# pulse_generator_pen.net
KiCad netlist of a schematic drawn in Altium Designer
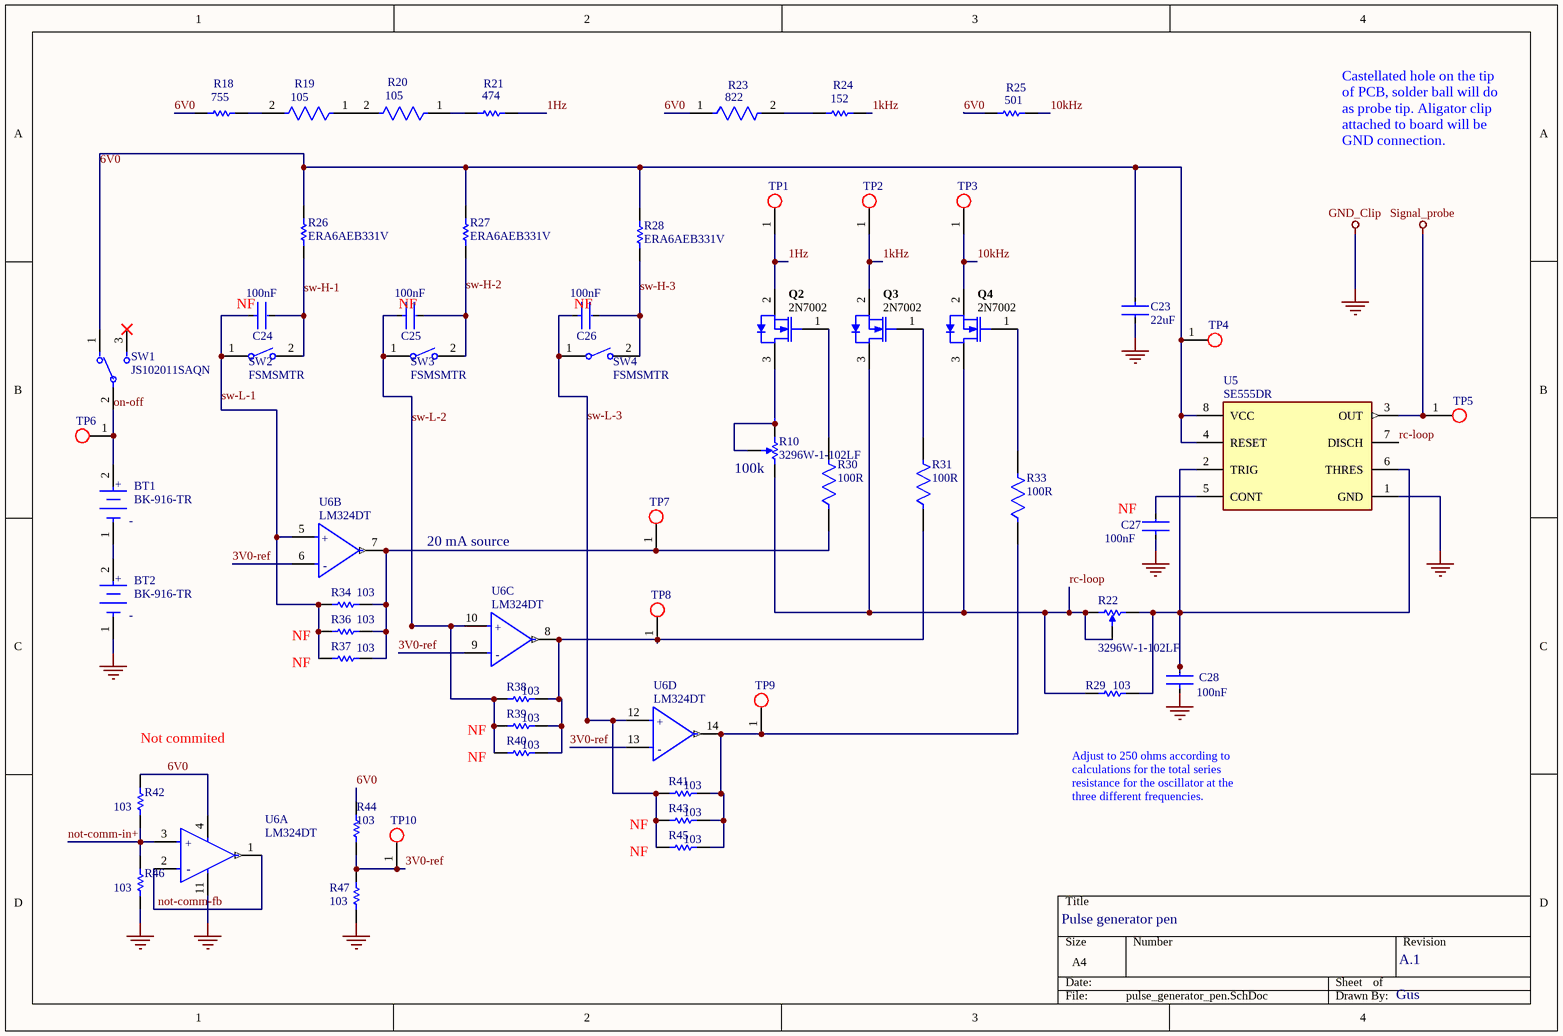
[diagram p0: pulse_generator_pen.SchDoc]

(export (version "E")
  (design (tool "Eeschema 10.0.6"))
  (components
    (comp (ref "BT1")
      (value "BK-916-TR")
      (footprint "FP-BK-916-TR-MFG")
      (description "BATTERY RETAINER COIN 12MM SMD")
      (libsource (lib "Altium Content Vault") (part "a5284bd3cf3b31494a5f032c79b9da8"))
    )
    (comp (ref "BT2")
      (value "BK-916-TR")
      (footprint "FP-BK-916-TR-MFG")
      (description "BATTERY RETAINER COIN 12MM SMD")
      (libsource (lib "Altium Content Vault") (part "a5284bd3cf3b31494a5f032c79b9da8"))
    )
    (comp (ref "C23")
      (value "C2012X5R1V226M125AC")
      (footprint "FP-C2012-125-0_2-IPC_A")
      (description "Multilayer Ceramic Capacitors 22μF ±20% 35V X5R SMD 0805")
      (fields (field (name "TOLERANCE") "20%") (field (name "CAPACITANCE") "22uF"))
      (libsource (lib "Altium Content Vault") (part "b4654b650e69147ec39a6b967a45e02"))
    )
    (comp (ref "C24")
      (value "CL21B104KBCNNNC")
      (footprint "FP-CL21-IPC_A")
      (description "CL21 Series 0805 100nF 50V ±10% Tolerance X7R Multilayer Ceramic Chip Capacitor")
      (fields
        (field (name "TOLERANCE") "10%")
        (field (name "CAPACITANCE") "100nF")
        (field (name "VOLTAGE") "50V")
      )
      (libsource (lib "Altium Content Vault") (part "b4654b650e69147ec39a6b967a45e02"))
    )
    (comp (ref "C25")
      (value "CL21B104KBCNNNC")
      (footprint "FP-CL21-IPC_A")
      (description "CL21 Series 0805 100nF 50V ±10% Tolerance X7R Multilayer Ceramic Chip Capacitor")
      (fields
        (field (name "TOLERANCE") "10%")
        (field (name "CAPACITANCE") "100nF")
        (field (name "VOLTAGE") "50V")
      )
      (libsource (lib "Altium Content Vault") (part "b4654b650e69147ec39a6b967a45e02"))
    )
    (comp (ref "C26")
      (value "CL21B104KBCNNNC")
      (footprint "FP-CL21-IPC_A")
      (description "CL21 Series 0805 100nF 50V ±10% Tolerance X7R Multilayer Ceramic Chip Capacitor")
      (fields
        (field (name "TOLERANCE") "10%")
        (field (name "CAPACITANCE") "100nF")
        (field (name "VOLTAGE") "50V")
      )
      (libsource (lib "Altium Content Vault") (part "b4654b650e69147ec39a6b967a45e02"))
    )
    (comp (ref "C27")
      (value "CL21B104KBCNNNC")
      (footprint "FP-CL21-IPC_A")
      (description "CL21 Series 0805 100nF 50V ±10% Tolerance X7R Multilayer Ceramic Chip Capacitor")
      (fields
        (field (name "TOLERANCE") "10%")
        (field (name "CAPACITANCE") "100nF")
        (field (name "VOLTAGE") "50V")
      )
      (libsource (lib "Altium Content Vault") (part "b4654b650e69147ec39a6b967a45e02"))
    )
    (comp (ref "C28")
      (value "CL21B104KBCNNNC")
      (footprint "FP-CL21-IPC_A")
      (description "CL21 Series 0805 100nF 50V ±10% Tolerance X7R Multilayer Ceramic Chip Capacitor")
      (fields
        (field (name "TOLERANCE") "10%")
        (field (name "CAPACITANCE") "100nF")
        (field (name "VOLTAGE") "50V")
      )
      (libsource (lib "Altium Content Vault") (part "b4654b650e69147ec39a6b967a45e02"))
    )
    (comp (ref "Q2")
      (value "2N7002")
      (footprint "INF-PG-SOT23_M")
      (fields (field (name "MANUFACTURER") "Infineon"))
      (libsource (lib "Altium Content Vault") (part "INF-NDMOS-GSD-3"))
    )
    (comp (ref "Q3")
      (value "2N7002")
      (footprint "INF-PG-SOT23_M")
      (fields (field (name "MANUFACTURER") "Infineon"))
      (libsource (lib "Altium Content Vault") (part "INF-NDMOS-GSD-3"))
    )
    (comp (ref "Q4")
      (value "2N7002")
      (footprint "INF-PG-SOT23_M")
      (fields (field (name "MANUFACTURER") "Infineon"))
      (libsource (lib "Altium Content Vault") (part "INF-NDMOS-GSD-3"))
    )
    (comp (ref "R10")
      (value "3296W-1-102LF")
      (footprint "BOUR-3296W-1-3")
      (description "Square Trimpot(R) Trimming Potentiometer, 1000 Ohm, -55 to 125 degC, 3-Pin THD, RoHS, Tube")
      (fields (field (name "TOLERANCE") "1%"))
      (libsource (lib "Altium Content Vault") (part "RES-ADJ-3"))
    )
    (comp (ref "R18")
      (value "CRCW08057M50JNEA")
      (footprint "RESC2013X50X30LL20T20")
      (fields (field (name "MANUFACTURER") "Vishay Dale") (field (name "RESISTANCE") "755"))
      (libsource (lib "Altium Content Vault") (part "RES"))
    )
    (comp (ref "R19")
      (value "ERJ-6ENF1004V")
      (footprint "FP-ERJ6EN-IPC_A")
      (description "RES SMD 1M OHM 1% 1/8W 0805")
      (fields (field (name "RESISTANCE") "105") (field (name "TOLERANCE") "1%"))
      (libsource (lib "Altium Content Vault") (part "1029c3af85768c4190bb7ad29bc67b5"))
    )
    (comp (ref "R20")
      (value "ERJ-6ENF1004V")
      (footprint "FP-ERJ6EN-IPC_A")
      (description "RES SMD 1M OHM 1% 1/8W 0805")
      (fields (field (name "RESISTANCE") "105") (field (name "TOLERANCE") "1%"))
      (libsource (lib "Altium Content Vault") (part "1029c3af85768c4190bb7ad29bc67b5"))
    )
    (comp (ref "R21")
      (value "ERJ6ENF4703V")
      (footprint "RESC2013X70X40ML20T20")
      (fields (field (name "MANUFACTURER") "Panasonic") (field (name "RESISTANCE") "474"))
      (libsource (lib "Altium Content Vault") (part "RES"))
    )
    (comp (ref "R22")
      (value "3296W-1-102LF")
      (footprint "BOUR-3296W-1-3")
      (description "Square Trimpot(R) Trimming Potentiometer, 1000 Ohm, -55 to 125 degC, 3-Pin THD, RoHS, Tube")
      (fields (field (name "TOLERANCE") "1%"))
      (libsource (lib "Altium Content Vault") (part "RES-ADJ-3"))
    )
    (comp (ref "R23")
      (value "RC2012J822CS")
      (footprint "FP-RC2012-IPC_A")
      (description "Res Thick Film 0805 8.2kΩ 5% 0.125W ±100ppm/°C Molded SMD T/R")
      (fields (field (name "RESISTANCE") "822") (field (name "TOLERANCE") "5%"))
      (libsource (lib "Altium Content Vault") (part "1029c3af85768c4190bb7ad29bc67b5"))
    )
    (comp (ref "R24")
      (value "RC0805FR-071K5L")
      (footprint "RESC2013X60X35LL10T20")
      (description "RES 1.50K OHM 1/8W 1% 0805 SMD")
      (fields (field (name "MANUFACTURER") "Yageo") (field (name "RESISTANCE") "152"))
      (libsource (lib "") (part "RES-2_1"))
    )
    (comp (ref "R25")
      (value "WSLP0805R0500FEA")
      (footprint "RESC2013X58X38LL25T25")
      (fields (field (name "MANUFACTURER") "Vishay Dale") (field (name "RESISTANCE") "501"))
      (libsource (lib "Altium Content Vault") (part "RES"))
    )
    (comp (ref "R26")
      (value "ERA6AEB331V")
      (footprint "RESC2013X60X40LL20T25")
      (fields (field (name "MANUFACTURER") "Panasonic"))
      (libsource (lib "Altium Content Vault") (part "RES"))
    )
    (comp (ref "R27")
      (value "ERA6AEB331V")
      (footprint "RESC2013X60X40LL20T25")
      (fields (field (name "MANUFACTURER") "Panasonic"))
      (libsource (lib "Altium Content Vault") (part "RES"))
    )
    (comp (ref "R28")
      (value "ERA6AEB331V")
      (footprint "RESC2013X60X40LL20T25")
      (fields (field (name "MANUFACTURER") "Panasonic"))
      (libsource (lib "Altium Content Vault") (part "RES"))
    )
    (comp (ref "R29")
      (value "RC0805FR-0710KL")
      (footprint "RESC2013X60X35NL10T20")
      (description "Chip Resistor, 10 KOhm, +/- 1%, 0.125 W, -55 to 155 degC, 0805 (2012 Metric), RoHS, Tape and Reel")
      (fields (field (name "MANUFACTURER") "Yageo") (field (name "RESISTANCE") "103"))
      (libsource (lib "Altium Content Vault") (part "RES-2"))
    )
    (comp (ref "R30")
      (value "CRCW0805100RFKEAHP")
      (footprint "FP-CRCW0805-HPe3-IPC_A")
      (description "RES Thick Film, 100Ω, 1%, 0.5W, 100ppm/°C, 0805")
      (fields (field (name "TOLERANCE") "1%") (field (name "RESISTANCE") "100R"))
      (libsource (lib "") (part "1029c3af85768c4190bb7ad29bc67b5_1"))
    )
    (comp (ref "R31")
      (value "CRCW0805100RFKEAHP")
      (footprint "FP-CRCW0805-HPe3-IPC_A")
      (description "RES Thick Film, 100Ω, 1%, 0.5W, 100ppm/°C, 0805")
      (fields (field (name "TOLERANCE") "1%") (field (name "RESISTANCE") "100R"))
      (libsource (lib "") (part "1029c3af85768c4190bb7ad29bc67b5_1"))
    )
    (comp (ref "R33")
      (value "CRCW0805100RFKEAHP")
      (footprint "FP-CRCW0805-HPe3-IPC_A")
      (description "RES Thick Film, 100Ω, 1%, 0.5W, 100ppm/°C, 0805")
      (fields (field (name "TOLERANCE") "1%") (field (name "RESISTANCE") "100R"))
      (libsource (lib "") (part "1029c3af85768c4190bb7ad29bc67b5_1"))
    )
    (comp (ref "R34")
      (value "RC0805FR-0710KL")
      (footprint "RESC2013X60X35NL10T20")
      (description "Chip Resistor, 10 KOhm, +/- 1%, 0.125 W, -55 to 155 degC, 0805 (2012 Metric), RoHS, Tape and Reel")
      (fields (field (name "MANUFACTURER") "Yageo") (field (name "RESISTANCE") "103"))
      (libsource (lib "Altium Content Vault") (part "RES-2"))
    )
    (comp (ref "R36")
      (value "RC0805FR-0710KL")
      (footprint "RESC2013X60X35NL10T20")
      (description "Chip Resistor, 10 KOhm, +/- 1%, 0.125 W, -55 to 155 degC, 0805 (2012 Metric), RoHS, Tape and Reel")
      (fields (field (name "MANUFACTURER") "Yageo") (field (name "RESISTANCE") "103"))
      (libsource (lib "Altium Content Vault") (part "RES-2"))
    )
    (comp (ref "R37")
      (value "RC0805FR-0710KL")
      (footprint "RESC2013X60X35NL10T20")
      (description "Chip Resistor, 10 KOhm, +/- 1%, 0.125 W, -55 to 155 degC, 0805 (2012 Metric), RoHS, Tape and Reel")
      (fields (field (name "MANUFACTURER") "Yageo") (field (name "RESISTANCE") "103"))
      (libsource (lib "Altium Content Vault") (part "RES-2"))
    )
    (comp (ref "R38")
      (value "RC0805FR-0710KL")
      (footprint "RESC2013X60X35NL10T20")
      (description "Chip Resistor, 10 KOhm, +/- 1%, 0.125 W, -55 to 155 degC, 0805 (2012 Metric), RoHS, Tape and Reel")
      (fields (field (name "MANUFACTURER") "Yageo") (field (name "RESISTANCE") "103"))
      (libsource (lib "Altium Content Vault") (part "RES-2"))
    )
    (comp (ref "R39")
      (value "RC0805FR-0710KL")
      (footprint "RESC2013X60X35NL10T20")
      (description "Chip Resistor, 10 KOhm, +/- 1%, 0.125 W, -55 to 155 degC, 0805 (2012 Metric), RoHS, Tape and Reel")
      (fields (field (name "MANUFACTURER") "Yageo") (field (name "RESISTANCE") "103"))
      (libsource (lib "Altium Content Vault") (part "RES-2"))
    )
    (comp (ref "R40")
      (value "RC0805FR-0710KL")
      (footprint "RESC2013X60X35NL10T20")
      (description "Chip Resistor, 10 KOhm, +/- 1%, 0.125 W, -55 to 155 degC, 0805 (2012 Metric), RoHS, Tape and Reel")
      (fields (field (name "MANUFACTURER") "Yageo") (field (name "RESISTANCE") "103"))
      (libsource (lib "Altium Content Vault") (part "RES-2"))
    )
    (comp (ref "R41")
      (value "RC0805FR-0710KL")
      (footprint "RESC2013X60X35NL10T20")
      (description "Chip Resistor, 10 KOhm, +/- 1%, 0.125 W, -55 to 155 degC, 0805 (2012 Metric), RoHS, Tape and Reel")
      (fields (field (name "MANUFACTURER") "Yageo") (field (name "RESISTANCE") "103"))
      (libsource (lib "Altium Content Vault") (part "RES-2"))
    )
    (comp (ref "R42")
      (value "RC0805FR-0710KL")
      (footprint "RESC2013X60X35NL10T20")
      (description "Chip Resistor, 10 KOhm, +/- 1%, 0.125 W, -55 to 155 degC, 0805 (2012 Metric), RoHS, Tape and Reel")
      (fields (field (name "MANUFACTURER") "Yageo") (field (name "RESISTANCE") "103"))
      (libsource (lib "Altium Content Vault") (part "RES-2"))
    )
    (comp (ref "R43")
      (value "RC0805FR-0710KL")
      (footprint "RESC2013X60X35NL10T20")
      (description "Chip Resistor, 10 KOhm, +/- 1%, 0.125 W, -55 to 155 degC, 0805 (2012 Metric), RoHS, Tape and Reel")
      (fields (field (name "MANUFACTURER") "Yageo") (field (name "RESISTANCE") "103"))
      (libsource (lib "Altium Content Vault") (part "RES-2"))
    )
    (comp (ref "R44")
      (value "RC0805FR-0710KL")
      (footprint "RESC2013X60X35NL10T20")
      (description "Chip Resistor, 10 KOhm, +/- 1%, 0.125 W, -55 to 155 degC, 0805 (2012 Metric), RoHS, Tape and Reel")
      (fields (field (name "MANUFACTURER") "Yageo") (field (name "RESISTANCE") "103"))
      (libsource (lib "Altium Content Vault") (part "RES-2"))
    )
    (comp (ref "R45")
      (value "RC0805FR-0710KL")
      (footprint "RESC2013X60X35NL10T20")
      (description "Chip Resistor, 10 KOhm, +/- 1%, 0.125 W, -55 to 155 degC, 0805 (2012 Metric), RoHS, Tape and Reel")
      (fields (field (name "MANUFACTURER") "Yageo") (field (name "RESISTANCE") "103"))
      (libsource (lib "Altium Content Vault") (part "RES-2"))
    )
    (comp (ref "R46")
      (value "RC0805FR-0710KL")
      (footprint "RESC2013X60X35NL10T20")
      (description "Chip Resistor, 10 KOhm, +/- 1%, 0.125 W, -55 to 155 degC, 0805 (2012 Metric), RoHS, Tape and Reel")
      (fields (field (name "MANUFACTURER") "Yageo") (field (name "RESISTANCE") "103"))
      (libsource (lib "Altium Content Vault") (part "RES-2"))
    )
    (comp (ref "R47")
      (value "RC0805FR-0710KL")
      (footprint "RESC2013X60X35NL10T20")
      (description "Chip Resistor, 10 KOhm, +/- 1%, 0.125 W, -55 to 155 degC, 0805 (2012 Metric), RoHS, Tape and Reel")
      (fields (field (name "MANUFACTURER") "Yageo") (field (name "RESISTANCE") "103"))
      (libsource (lib "Altium Content Vault") (part "RES-2"))
    )
    (comp (ref "SW1")
      (value "JS102011SAQN")
      (footprint "FP-JS102011SAQN-MFG")
      (description "SWITCH SLIDE SPDT 300MA 6V")
      (libsource (lib "Altium Content Vault") (part "39e195cbbadc85d1df0d7eb6847d379"))
    )
    (comp (ref "SW2")
      (value "FSMSMTR")
      (footprint "TECO-FSMSMTR_V")
      (description "FSMSM Push Button Switch, 50 mA, -35 to 85 degC, 2-Pin SMD, RoHS, Tape and Reel")
      (fields (field (name "MANUFACTURER") "TE Connectivity"))
      (libsource (lib "Altium Content Vault") (part "SW-SPST-2_C"))
    )
    (comp (ref "SW3")
      (value "FSMSMTR")
      (footprint "TECO-FSMSMTR_V")
      (description "FSMSM Push Button Switch, 50 mA, -35 to 85 degC, 2-Pin SMD, RoHS, Tape and Reel")
      (fields (field (name "MANUFACTURER") "TE Connectivity"))
      (libsource (lib "Altium Content Vault") (part "SW-SPST-2_C"))
    )
    (comp (ref "SW4")
      (value "FSMSMTR")
      (footprint "TECO-FSMSMTR_V")
      (description "FSMSM Push Button Switch, 50 mA, -35 to 85 degC, 2-Pin SMD, RoHS, Tape and Reel")
      (fields (field (name "MANUFACTURER") "TE Connectivity"))
      (libsource (lib "Altium Content Vault") (part "SW-SPST-2_C"))
    )
    (comp (ref "TP1")
      (value "TP_opening")
      (footprint "New footprint 1")
      (description "Soldermask opening or top layer pad for testing purposes")
      (libsource (lib "Cetys University") (part "TP1"))
    )
    (comp (ref "TP2")
      (value "TP_opening")
      (footprint "New footprint 1")
      (description "Soldermask opening or top layer pad for testing purposes")
      (libsource (lib "Cetys University") (part "TP1"))
    )
    (comp (ref "TP3")
      (value "TP_opening")
      (footprint "New footprint 1")
      (description "Soldermask opening or top layer pad for testing purposes")
      (libsource (lib "Cetys University") (part "TP1"))
    )
    (comp (ref "TP4")
      (value "TP_opening")
      (footprint "New footprint 1")
      (description "Soldermask opening or top layer pad for testing purposes")
      (libsource (lib "Cetys University") (part "TP1"))
    )
    (comp (ref "TP5")
      (value "TP_opening")
      (footprint "New footprint 1")
      (description "Soldermask opening or top layer pad for testing purposes")
      (libsource (lib "Cetys University") (part "TP1"))
    )
    (comp (ref "TP6")
      (value "TP_opening")
      (footprint "New footprint 1")
      (description "Soldermask opening or top layer pad for testing purposes")
      (libsource (lib "Cetys University") (part "TP1"))
    )
    (comp (ref "TP7")
      (value "TP_opening")
      (footprint "New footprint 1")
      (description "Soldermask opening or top layer pad for testing purposes")
      (libsource (lib "Cetys University") (part "TP1"))
    )
    (comp (ref "TP8")
      (value "TP_opening")
      (footprint "New footprint 1")
      (description "Soldermask opening or top layer pad for testing purposes")
      (libsource (lib "Cetys University") (part "TP1"))
    )
    (comp (ref "TP9")
      (value "TP_opening")
      (footprint "New footprint 1")
      (description "Soldermask opening or top layer pad for testing purposes")
      (libsource (lib "Cetys University") (part "TP1"))
    )
    (comp (ref "TP10")
      (value "TP_opening")
      (footprint "New footprint 1")
      (description "Soldermask opening or top layer pad for testing purposes")
      (libsource (lib "Cetys University") (part "TP1"))
    )
    (comp (ref "U5")
      (value "SE555DR")
      (footprint "FP-D0008A-MFG")
      (description "IC OSC SGL TIMER 100KHZ 8-SOIC")
      (libsource (lib "Altium Content Vault") (part "dd5b8434f2346953fd8290325fbf3de"))
    )
    (comp (ref "U6")
      (value "LM324DT")
      (footprint "FP-SO-14-MFG")
      (description "IC OPAMP GP 4 CIRCUIT 14SO")
      (fields
        (field (name "OCTOPART") "https://octopart.com/lm324dt-stmicroelectronics-39579146")
        (field (name "MANUFACTURER") "STMicroelectronics")
      )
      (libsource (lib "Altium Content Vault") (part "a065ef67e5aa9ef3942d43d6008d043"))
    )
  )
  (nets
    (net (code "1") (name "/1Hz") (class "Default")
      (node (ref "Q2") (pin "2") (pinfunction "SOURCE_2") (pintype "passive"))
      (node (ref "R21") (pin "2") (pinfunction "2_2") (pintype "passive"))
      (node (ref "TP1") (pin "1") (pinfunction "1_1") (pintype "passive"))
    )
    (net (code "2") (name "/1kHz") (class "Default")
      (node (ref "Q3") (pin "2") (pinfunction "SOURCE_2") (pintype "passive"))
      (node (ref "R24") (pin "2") (pinfunction "2_2") (pintype "passive"))
      (node (ref "TP2") (pin "1") (pinfunction "1_1") (pintype "passive"))
    )
    (net (code "3") (name "/3V0-ref") (class "Default")
      (node (ref "R44") (pin "1") (pinfunction "1_1") (pintype "passive"))
      (node (ref "R47") (pin "2") (pinfunction "2_2") (pintype "passive"))
      (node (ref "TP10") (pin "1") (pinfunction "1_1") (pintype "passive"))
      (node (ref "U6") (pin "13") (pinfunction "Inverting_Input_4_13") (pintype "tri_state"))
      (node (ref "U6") (pin "6") (pinfunction "Inverting_Input_2_6") (pintype "tri_state"))
      (node (ref "U6") (pin "9") (pinfunction "Inverting_Input_3_9") (pintype "tri_state"))
    )
    (net (code "4") (name "/6V0") (class "Default")
      (node (ref "C23") (pin "1") (pinfunction "1_1") (pintype "passive"))
      (node (ref "R18") (pin "2") (pinfunction "2_2") (pintype "passive"))
      (node (ref "R23") (pin "1") (pinfunction "1_1") (pintype "passive"))
      (node (ref "R25") (pin "1") (pinfunction "1_1") (pintype "passive"))
      (node (ref "R26") (pin "1") (pinfunction "1_1") (pintype "passive"))
      (node (ref "R27") (pin "1") (pinfunction "1_1") (pintype "passive"))
      (node (ref "R28") (pin "1") (pinfunction "1_1") (pintype "passive"))
      (node (ref "R42") (pin "2") (pinfunction "2_2") (pintype "passive"))
      (node (ref "R44") (pin "2") (pinfunction "2_2") (pintype "passive"))
      (node (ref "SW1") (pin "1") (pinfunction "1_1") (pintype "passive"))
      (node (ref "TP4") (pin "1") (pinfunction "1_1") (pintype "passive"))
      (node (ref "U5") (pin "4") (pinfunction "RESET_4") (pintype "passive"))
      (node (ref "U5") (pin "8") (pinfunction "VCC_8") (pintype "power_in"))
      (node (ref "U6") (pin "4") (pinfunction "VCC+_4") (pintype "power_in"))
    )
    (net (code "5") (name "/10kHz") (class "Default")
      (node (ref "Q4") (pin "2") (pinfunction "SOURCE_2") (pintype "passive"))
      (node (ref "R25") (pin "2") (pinfunction "2_2") (pintype "passive"))
      (node (ref "TP3") (pin "1") (pinfunction "1_1") (pintype "passive"))
    )
    (net (code "6") (name "/not-comm-fb") (class "Default")
      (node (ref "U6") (pin "1") (pinfunction "Output_1_1") (pintype "output"))
      (node (ref "U6") (pin "2") (pinfunction "Inverting_Input_1_2") (pintype "tri_state"))
    )
    (net (code "7") (name "/not-comm-in+") (class "Default")
      (node (ref "R42") (pin "1") (pinfunction "1_1") (pintype "passive"))
      (node (ref "R46") (pin "2") (pinfunction "2_2") (pintype "passive"))
      (node (ref "U6") (pin "3") (pinfunction "Non-Inverting_Input_1_3") (pintype "tri_state"))
    )
    (net (code "8") (name "/on-off") (class "Default")
      (node (ref "BT1") (pin "2") (pinfunction "A_2") (pintype "passive"))
      (node (ref "SW1") (pin "2") (pinfunction "C_2") (pintype "passive"))
      (node (ref "TP6") (pin "1") (pinfunction "1_1") (pintype "passive"))
    )
    (net (code "9") (name "/rc-loop") (class "Default")
      (node (ref "Q3") (pin "3") (pinfunction "DRAIN_3") (pintype "passive"))
      (node (ref "Q4") (pin "3") (pinfunction "DRAIN_3") (pintype "passive"))
      (node (ref "R10") (pin "2") (pinfunction "B_2") (pintype "passive"))
      (node (ref "R22") (pin "1") (pinfunction "A_1") (pintype "passive"))
      (node (ref "R22") (pin "3") (pinfunction "TAP_3") (pintype "passive"))
      (node (ref "R29") (pin "2") (pinfunction "2_2") (pintype "passive"))
      (node (ref "U5") (pin "7") (pinfunction "DISCH_7") (pintype "passive"))
    )
    (net (code "10") (name "/sw-H-1") (class "Default")
      (node (ref "C24") (pin "2") (pinfunction "2_2") (pintype "passive"))
      (node (ref "R26") (pin "2") (pinfunction "2_2") (pintype "passive"))
      (node (ref "SW2") (pin "2") (pinfunction "2_2") (pintype "passive"))
    )
    (net (code "11") (name "/sw-H-2") (class "Default")
      (node (ref "C25") (pin "2") (pinfunction "2_2") (pintype "passive"))
      (node (ref "R27") (pin "2") (pinfunction "2_2") (pintype "passive"))
      (node (ref "SW3") (pin "2") (pinfunction "2_2") (pintype "passive"))
    )
    (net (code "12") (name "/sw-H-3") (class "Default")
      (node (ref "C26") (pin "2") (pinfunction "2_2") (pintype "passive"))
      (node (ref "R28") (pin "2") (pinfunction "2_2") (pintype "passive"))
      (node (ref "SW4") (pin "2") (pinfunction "2_2") (pintype "passive"))
    )
    (net (code "13") (name "/sw-L-1") (class "Default")
      (node (ref "C24") (pin "1") (pinfunction "1_1") (pintype "passive"))
      (node (ref "R34") (pin "2") (pinfunction "2_2") (pintype "passive"))
      (node (ref "R36") (pin "2") (pinfunction "2_2") (pintype "passive"))
      (node (ref "R37") (pin "2") (pinfunction "2_2") (pintype "passive"))
      (node (ref "SW2") (pin "1") (pinfunction "1_1") (pintype "passive"))
      (node (ref "U6") (pin "5") (pinfunction "Non-Inverting_Input_2_5") (pintype "tri_state"))
    )
    (net (code "14") (name "/sw-L-2") (class "Default")
      (node (ref "C25") (pin "1") (pinfunction "1_1") (pintype "passive"))
      (node (ref "R38") (pin "2") (pinfunction "2_2") (pintype "passive"))
      (node (ref "R39") (pin "2") (pinfunction "2_2") (pintype "passive"))
      (node (ref "R40") (pin "2") (pinfunction "2_2") (pintype "passive"))
      (node (ref "SW3") (pin "1") (pinfunction "1_1") (pintype "passive"))
      (node (ref "U6") (pin "10") (pinfunction "Non-Inverting_Input_3_10") (pintype "tri_state"))
    )
    (net (code "15") (name "/sw-L-3") (class "Default")
      (node (ref "C26") (pin "1") (pinfunction "1_1") (pintype "passive"))
      (node (ref "R41") (pin "2") (pinfunction "2_2") (pintype "passive"))
      (node (ref "R43") (pin "2") (pinfunction "2_2") (pintype "passive"))
      (node (ref "R45") (pin "2") (pinfunction "2_2") (pintype "passive"))
      (node (ref "SW4") (pin "1") (pinfunction "1_1") (pintype "passive"))
      (node (ref "U6") (pin "12") (pinfunction "Non-Inverting_Input_4_12") (pintype "tri_state"))
    )
    (net (code "16") (name "GND") (class "Default")
      (node (ref "BT2") (pin "1") (pinfunction "C_1") (pintype "passive"))
      (node (ref "C23") (pin "2") (pinfunction "2_2") (pintype "passive"))
      (node (ref "C27") (pin "1") (pinfunction "1_1") (pintype "passive"))
      (node (ref "C28") (pin "1") (pinfunction "1_1") (pintype "passive"))
      (node (ref "R46") (pin "1") (pinfunction "1_1") (pintype "passive"))
      (node (ref "R47") (pin "1") (pinfunction "1_1") (pintype "passive"))
      (node (ref "U5") (pin "1") (pinfunction "GND_1") (pintype "power_in"))
      (node (ref "U6") (pin "11") (pinfunction "VCC-_11") (pintype "power_in"))
    )
    (net (code "17") (name "Net-(BT1-C)") (class "Default")
      (node (ref "BT1") (pin "1") (pinfunction "C_1") (pintype "passive"))
      (node (ref "BT2") (pin "2") (pinfunction "A_2") (pintype "passive"))
    )
    (net (code "18") (name "Net-(Q2-DRAIN)") (class "Default")
      (node (ref "Q2") (pin "3") (pinfunction "DRAIN_3") (pintype "passive"))
      (node (ref "R10") (pin "1") (pinfunction "A_1") (pintype "passive"))
      (node (ref "R10") (pin "3") (pinfunction "TAP_3") (pintype "passive"))
    )
    (net (code "19") (name "Net-(Q2-GATE)") (class "Default")
      (node (ref "Q2") (pin "1") (pinfunction "GATE_1") (pintype "passive"))
      (node (ref "R30") (pin "2") (pinfunction "2_2") (pintype "passive"))
    )
    (net (code "20") (name "Net-(Q3-GATE)") (class "Default")
      (node (ref "Q3") (pin "1") (pinfunction "GATE_1") (pintype "passive"))
      (node (ref "R31") (pin "2") (pinfunction "2_2") (pintype "passive"))
    )
    (net (code "21") (name "Net-(Q4-GATE)") (class "Default")
      (node (ref "Q4") (pin "1") (pinfunction "GATE_1") (pintype "passive"))
      (node (ref "R33") (pin "2") (pinfunction "2_2") (pintype "passive"))
    )
    (net (code "22") (name "Net-(R18-Pad1)") (class "Default")
      (node (ref "R18") (pin "1") (pinfunction "1_1") (pintype "passive"))
      (node (ref "R19") (pin "2") (pinfunction "2_2") (pintype "passive"))
    )
    (net (code "23") (name "Net-(R19-Pad1)") (class "Default")
      (node (ref "R19") (pin "1") (pinfunction "1_1") (pintype "passive"))
      (node (ref "R20") (pin "2") (pinfunction "2_2") (pintype "passive"))
    )
    (net (code "24") (name "Net-(R20-Pad1)") (class "Default")
      (node (ref "R20") (pin "1") (pinfunction "1_1") (pintype "passive"))
      (node (ref "R21") (pin "1") (pinfunction "1_1") (pintype "passive"))
    )
    (net (code "25") (name "Net-(R22-B)") (class "Default")
      (node (ref "C28") (pin "2") (pinfunction "2_2") (pintype "passive"))
      (node (ref "R22") (pin "2") (pinfunction "B_2") (pintype "passive"))
      (node (ref "R29") (pin "1") (pinfunction "1_1") (pintype "passive"))
      (node (ref "U5") (pin "2") (pinfunction "TRIG_2") (pintype "passive"))
      (node (ref "U5") (pin "6") (pinfunction "THRES_6") (pintype "passive"))
    )
    (net (code "26") (name "Net-(R23-Pad2)") (class "Default")
      (node (ref "R23") (pin "2") (pinfunction "2_2") (pintype "passive"))
      (node (ref "R24") (pin "1") (pinfunction "1_1") (pintype "passive"))
    )
    (net (code "27") (name "Net-(U5-CONT)") (class "Default")
      (node (ref "C27") (pin "2") (pinfunction "2_2") (pintype "passive"))
      (node (ref "U5") (pin "5") (pinfunction "CONT_5") (pintype "passive"))
    )
    (net (code "28") (name "Net-(U6B-Output_2)") (class "Default")
      (node (ref "R30") (pin "1") (pinfunction "1_1") (pintype "passive"))
      (node (ref "R34") (pin "1") (pinfunction "1_1") (pintype "passive"))
      (node (ref "R36") (pin "1") (pinfunction "1_1") (pintype "passive"))
      (node (ref "R37") (pin "1") (pinfunction "1_1") (pintype "passive"))
      (node (ref "TP7") (pin "1") (pinfunction "1_1") (pintype "passive"))
      (node (ref "U6") (pin "7") (pinfunction "Output_2_7") (pintype "output"))
    )
    (net (code "29") (name "Net-(U6C-Output_3)") (class "Default")
      (node (ref "R31") (pin "1") (pinfunction "1_1") (pintype "passive"))
      (node (ref "R38") (pin "1") (pinfunction "1_1") (pintype "passive"))
      (node (ref "R39") (pin "1") (pinfunction "1_1") (pintype "passive"))
      (node (ref "R40") (pin "1") (pinfunction "1_1") (pintype "passive"))
      (node (ref "TP8") (pin "1") (pinfunction "1_1") (pintype "passive"))
      (node (ref "U6") (pin "8") (pinfunction "Output_3_8") (pintype "output"))
    )
    (net (code "30") (name "Net-(U6D-Output_4)") (class "Default")
      (node (ref "R33") (pin "1") (pinfunction "1_1") (pintype "passive"))
      (node (ref "R41") (pin "1") (pinfunction "1_1") (pintype "passive"))
      (node (ref "R43") (pin "1") (pinfunction "1_1") (pintype "passive"))
      (node (ref "R45") (pin "1") (pinfunction "1_1") (pintype "passive"))
      (node (ref "TP9") (pin "1") (pinfunction "1_1") (pintype "passive"))
      (node (ref "U6") (pin "14") (pinfunction "Output_4_14") (pintype "output"))
    )
    (net (code "31") (name "Signal_probe") (class "Default")
      (node (ref "TP5") (pin "1") (pinfunction "1_1") (pintype "passive"))
      (node (ref "U5") (pin "3") (pinfunction "OUT_3") (pintype "output"))
    )
    (net (code "32") (name "unconnected-(SW1-Pad3)") (class "Default")
      (node (ref "SW1") (pin "3") (pinfunction "3_3") (pintype "passive+no_connect"))
    )
  )
)
